# pcb.net
KiCad netlist of a schematic drawn in EAGLE
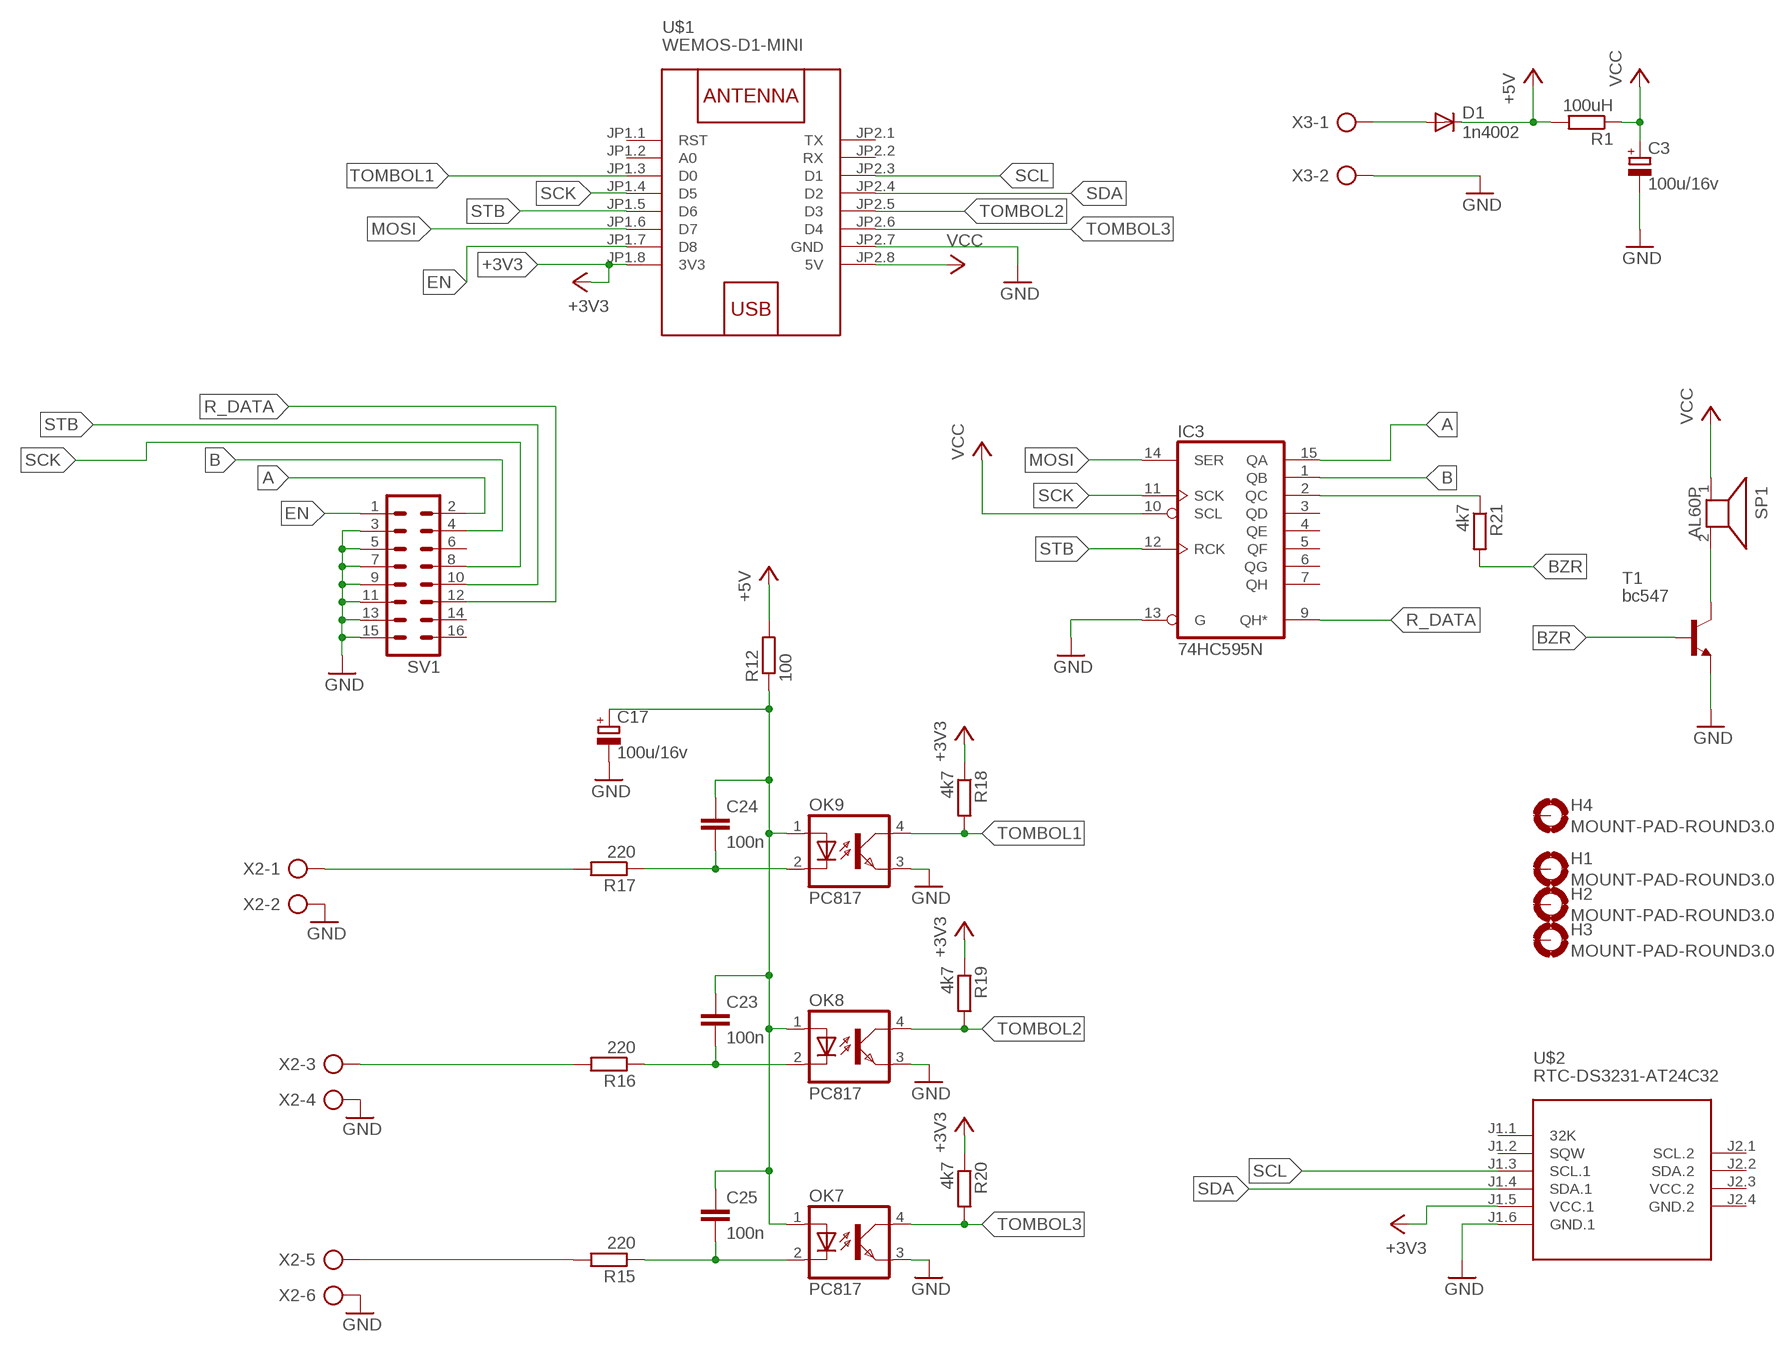
[diagram p0: schematic, sheet 1]

(export (version "E")
  (design (tool "Eeschema 10.0.6"))
  (components
    (comp (ref "C3")
      (value "100u/16v")
      (footprint "eagle-import:E5-4")
      (libsource (lib "eagle-import") (part "CPOL-EUE5-4"))
    )
    (comp (ref "C17")
      (value "100u/16v")
      (footprint "eagle-import:E5-4")
      (libsource (lib "eagle-import") (part "CPOL-EUE5-4"))
    )
    (comp (ref "C23")
      (value "100n")
      (footprint "eagle-import:C050-025X075")
      (libsource (lib "eagle-import") (part "C-EU050-025X075"))
    )
    (comp (ref "C24")
      (value "100n")
      (footprint "eagle-import:C050-025X075")
      (libsource (lib "eagle-import") (part "C-EU050-025X075"))
    )
    (comp (ref "C25")
      (value "100n")
      (footprint "eagle-import:C050-025X075")
      (libsource (lib "eagle-import") (part "C-EU050-025X075"))
    )
    (comp (ref "D1")
      (value "1n4002")
      (footprint "eagle-import:DO35-10")
      (libsource (lib "eagle-import") (part "1N4446"))
    )
    (comp (ref "H1")
      (value "MOUNT-PAD-ROUND3.0")
      (footprint "eagle-import:3,0-PAD")
      (libsource (lib "eagle-import") (part "MOUNT-PAD-ROUND3.0"))
    )
    (comp (ref "H2")
      (value "MOUNT-PAD-ROUND3.0")
      (footprint "eagle-import:3,0-PAD")
      (libsource (lib "eagle-import") (part "MOUNT-PAD-ROUND3.0"))
    )
    (comp (ref "H3")
      (value "MOUNT-PAD-ROUND3.0")
      (footprint "eagle-import:3,0-PAD")
      (libsource (lib "eagle-import") (part "MOUNT-PAD-ROUND3.0"))
    )
    (comp (ref "H4")
      (value "MOUNT-PAD-ROUND3.0")
      (footprint "eagle-import:3,0-PAD")
      (libsource (lib "eagle-import") (part "MOUNT-PAD-ROUND3.0"))
    )
    (comp (ref "IC3")
      (value "74HC595N")
      (footprint "eagle-import:DIL16")
      (libsource (lib "eagle-import") (part "74595NHC"))
    )
    (comp (ref "OK7")
      (value "PC817")
      (footprint "eagle-import:DIL04")
      (fields (field (name "MPN") "PC817X4J000F"))
      (libsource (lib "eagle-import") (part "PC817"))
    )
    (comp (ref "OK8")
      (value "PC817")
      (footprint "eagle-import:DIL04")
      (fields (field (name "MPN") "PC817X4J000F"))
      (libsource (lib "eagle-import") (part "PC817"))
    )
    (comp (ref "OK9")
      (value "PC817")
      (footprint "eagle-import:DIL04")
      (fields (field (name "MPN") "PC817X4J000F"))
      (libsource (lib "eagle-import") (part "PC817"))
    )
    (comp (ref "R1")
      (value "100uH")
      (footprint "eagle-import:0207_10")
      (libsource (lib "eagle-import") (part "R-EU_0207/10"))
    )
    (comp (ref "R12")
      (value "100")
      (footprint "eagle-import:0207_10")
      (libsource (lib "eagle-import") (part "R-EU_0207/10"))
    )
    (comp (ref "R15")
      (value "220")
      (footprint "eagle-import:0207_10")
      (libsource (lib "eagle-import") (part "R-EU_0207/10"))
    )
    (comp (ref "R16")
      (value "220")
      (footprint "eagle-import:0207_10")
      (libsource (lib "eagle-import") (part "R-EU_0207/10"))
    )
    (comp (ref "R17")
      (value "220")
      (footprint "eagle-import:0207_10")
      (libsource (lib "eagle-import") (part "R-EU_0207/10"))
    )
    (comp (ref "R18")
      (value "4k7")
      (footprint "eagle-import:0207_10")
      (libsource (lib "eagle-import") (part "R-EU_0207/10"))
    )
    (comp (ref "R19")
      (value "4k7")
      (footprint "eagle-import:0207_10")
      (libsource (lib "eagle-import") (part "R-EU_0207/10"))
    )
    (comp (ref "R20")
      (value "4k7")
      (footprint "eagle-import:0207_10")
      (libsource (lib "eagle-import") (part "R-EU_0207/10"))
    )
    (comp (ref "R21")
      (value "4k7")
      (footprint "eagle-import:0207_10")
      (libsource (lib "eagle-import") (part "R-EU_0207/10"))
    )
    (comp (ref "SP1")
      (value "AL60P")
      (footprint "eagle-import:AL60P")
      (libsource (lib "eagle-import") (part "AL60P"))
    )
    (comp (ref "SV1")
      (value "ML16")
      (footprint "eagle-import:ML16")
      (libsource (lib "eagle-import") (part "ML16"))
    )
    (comp (ref "T1")
      (value "bc547")
      (footprint "eagle-import:TO92-CBE")
      (libsource (lib "eagle-import") (part "-NPN-TO92-CBEBC547A"))
    )
    (comp (ref "U$1")
      (value "WEMOS-D1-MINI")
      (footprint "eagle-import:WEMOS-D1-MINI")
      (libsource (lib "eagle-import") (part "WEMOS-D1-MINI"))
    )
    (comp (ref "U$2")
      (value "RTC-DS3231-AT24C32")
      (footprint "eagle-import:RTC-DS3231-AT24C32")
      (libsource (lib "eagle-import") (part "RTC-DS3231-AT24C32"))
    )
    (comp (ref "X2")
      (value "AK300/6")
      (footprint "eagle-import:AK300_6")
      (libsource (lib "eagle-import") (part "AK300/6"))
    )
    (comp (ref "X3")
      (value "AK300/2")
      (footprint "eagle-import:AK300_2")
      (libsource (lib "eagle-import") (part "AK300/2"))
    )
  )
  (nets
    (net (code "1") (name "+3V3") (class "Default")
      (node (ref "R18") (pin "1") (pinfunction "1_1") (pintype "passive"))
      (node (ref "R19") (pin "1") (pinfunction "1_1") (pintype "passive"))
      (node (ref "R20") (pin "1") (pinfunction "1_1") (pintype "passive"))
      (node (ref "U$1") (pin "JP1.8") (pinfunction "3V3_JP1.8") (pintype "power_in"))
      (node (ref "U$2") (pin "J1.5") (pinfunction "VCC.1_J1.5") (pintype "power_in"))
    )
    (net (code "2") (name "+5V") (class "Default")
      (node (ref "D1") (pin "C") (pinfunction "C_C") (pintype "passive"))
      (node (ref "R1") (pin "2") (pinfunction "2_2") (pintype "passive"))
      (node (ref "R12") (pin "2") (pinfunction "2_2") (pintype "passive"))
    )
    (net (code "3") (name "/GND.2") (class "Default")
      (node (ref "U$2") (pin "J2.4") (pinfunction "GND.2_J2.4") (pintype "power_in"))
    )
    (net (code "4") (name "/VCC.2") (class "Default")
      (node (ref "U$2") (pin "J2.3") (pinfunction "VCC.2_J2.3") (pintype "power_in"))
    )
    (net (code "5") (name "A") (class "Default")
      (node (ref "IC3") (pin "15") (pinfunction "QA_15") (pintype "tri_state"))
      (node (ref "SV1") (pin "2") (pinfunction "2_2") (pintype "passive"))
    )
    (net (code "6") (name "B") (class "Default")
      (node (ref "IC3") (pin "1") (pinfunction "QB_1") (pintype "tri_state"))
      (node (ref "SV1") (pin "4") (pinfunction "4_4") (pintype "passive"))
    )
    (net (code "7") (name "BZR") (class "Default")
      (node (ref "R21") (pin "2") (pinfunction "2_2") (pintype "passive"))
      (node (ref "T1") (pin "B") (pinfunction "B_B") (pintype "passive"))
    )
    (net (code "8") (name "EN") (class "Default")
      (node (ref "SV1") (pin "1") (pinfunction "1_1") (pintype "passive"))
      (node (ref "U$1") (pin "JP1.7") (pinfunction "D8_JP1.7") (pintype "bidirectional"))
    )
    (net (code "9") (name "GND") (class "Default")
      (node (ref "C17") (pin "-") (pinfunction "-_-") (pintype "passive"))
      (node (ref "C3") (pin "-") (pinfunction "-_-") (pintype "passive"))
      (node (ref "IC3") (pin "13") (pinfunction "G_13") (pintype "input"))
      (node (ref "OK7") (pin "3") (pinfunction "EMIT_3") (pintype "passive"))
      (node (ref "OK8") (pin "3") (pinfunction "EMIT_3") (pintype "passive"))
      (node (ref "OK9") (pin "3") (pinfunction "EMIT_3") (pintype "passive"))
      (node (ref "SV1") (pin "11") (pinfunction "11_11") (pintype "passive"))
      (node (ref "SV1") (pin "13") (pinfunction "13_13") (pintype "passive"))
      (node (ref "SV1") (pin "15") (pinfunction "15_15") (pintype "passive"))
      (node (ref "SV1") (pin "3") (pinfunction "3_3") (pintype "passive"))
      (node (ref "SV1") (pin "5") (pinfunction "5_5") (pintype "passive"))
      (node (ref "SV1") (pin "7") (pinfunction "7_7") (pintype "passive"))
      (node (ref "SV1") (pin "9") (pinfunction "9_9") (pintype "passive"))
      (node (ref "T1") (pin "E") (pinfunction "E_E") (pintype "passive"))
      (node (ref "U$1") (pin "JP2.7") (pinfunction "GND_JP2.7") (pintype "power_in"))
      (node (ref "U$2") (pin "J1.6") (pinfunction "GND.1_J1.6") (pintype "power_in"))
      (node (ref "X2") (pin "2") (pinfunction "KL_2") (pintype "passive"))
      (node (ref "X2") (pin "4") (pinfunction "KL_4") (pintype "passive"))
      (node (ref "X2") (pin "6") (pinfunction "KL_6") (pintype "passive"))
      (node (ref "X3") (pin "2") (pinfunction "KL_2") (pintype "passive"))
    )
    (net (code "10") (name "MOSI") (class "Default")
      (node (ref "IC3") (pin "14") (pinfunction "SER_14") (pintype "input"))
      (node (ref "U$1") (pin "JP1.6") (pinfunction "D7_JP1.6") (pintype "bidirectional"))
    )
    (net (code "11") (name "Net-(IC3A-QC)") (class "Default")
      (node (ref "IC3") (pin "2") (pinfunction "QC_2") (pintype "tri_state"))
      (node (ref "R21") (pin "1") (pinfunction "1_1") (pintype "passive"))
    )
    (net (code "12") (name "Net-(OK7-A)") (class "Default")
      (node (ref "C17") (pin "+") (pinfunction "+_+") (pintype "passive"))
      (node (ref "C23") (pin "1") (pinfunction "1_1") (pintype "passive"))
      (node (ref "C24") (pin "1") (pinfunction "1_1") (pintype "passive"))
      (node (ref "C25") (pin "1") (pinfunction "1_1") (pintype "passive"))
      (node (ref "OK7") (pin "1") (pinfunction "A_1") (pintype "passive"))
      (node (ref "OK8") (pin "1") (pinfunction "A_1") (pintype "passive"))
      (node (ref "OK9") (pin "1") (pinfunction "A_1") (pintype "passive"))
      (node (ref "R12") (pin "1") (pinfunction "1_1") (pintype "passive"))
    )
    (net (code "13") (name "Net-(OK7-C)") (class "Default")
      (node (ref "C25") (pin "2") (pinfunction "2_2") (pintype "passive"))
      (node (ref "OK7") (pin "2") (pinfunction "C_2") (pintype "passive"))
      (node (ref "R15") (pin "1") (pinfunction "1_1") (pintype "passive"))
    )
    (net (code "14") (name "Net-(OK8-C)") (class "Default")
      (node (ref "C23") (pin "2") (pinfunction "2_2") (pintype "passive"))
      (node (ref "OK8") (pin "2") (pinfunction "C_2") (pintype "passive"))
      (node (ref "R16") (pin "1") (pinfunction "1_1") (pintype "passive"))
    )
    (net (code "15") (name "Net-(OK9-C)") (class "Default")
      (node (ref "C24") (pin "2") (pinfunction "2_2") (pintype "passive"))
      (node (ref "OK9") (pin "2") (pinfunction "C_2") (pintype "passive"))
      (node (ref "R17") (pin "1") (pinfunction "1_1") (pintype "passive"))
    )
    (net (code "16") (name "Net-(SP1-Pad2)") (class "Default")
      (node (ref "SP1") (pin "2") (pinfunction "2_2") (pintype "passive"))
      (node (ref "T1") (pin "C") (pinfunction "C_C") (pintype "passive"))
    )
    (net (code "17") (name "Net-(X2A-KL)") (class "Default")
      (node (ref "R17") (pin "2") (pinfunction "2_2") (pintype "passive"))
      (node (ref "X2") (pin "1") (pinfunction "KL_1") (pintype "passive"))
    )
    (net (code "18") (name "Net-(X2C-KL)") (class "Default")
      (node (ref "R16") (pin "2") (pinfunction "2_2") (pintype "passive"))
      (node (ref "X2") (pin "3") (pinfunction "KL_3") (pintype "passive"))
    )
    (net (code "19") (name "Net-(X2E-KL)") (class "Default")
      (node (ref "R15") (pin "2") (pinfunction "2_2") (pintype "passive"))
      (node (ref "X2") (pin "5") (pinfunction "KL_5") (pintype "passive"))
    )
    (net (code "20") (name "Net-(X3A-KL)") (class "Default")
      (node (ref "D1") (pin "A") (pinfunction "A_A") (pintype "passive"))
      (node (ref "X3") (pin "1") (pinfunction "KL_1") (pintype "passive"))
    )
    (net (code "21") (name "R_DATA") (class "Default")
      (node (ref "IC3") (pin "9") (pinfunction "QH*_9") (pintype "tri_state"))
      (node (ref "SV1") (pin "12") (pinfunction "12_12") (pintype "passive"))
    )
    (net (code "22") (name "SCK") (class "Default")
      (node (ref "IC3") (pin "11") (pinfunction "SCK_11") (pintype "input"))
      (node (ref "SV1") (pin "8") (pinfunction "8_8") (pintype "passive"))
      (node (ref "U$1") (pin "JP1.4") (pinfunction "D5_JP1.4") (pintype "bidirectional"))
    )
    (net (code "23") (name "SCL") (class "Default")
      (node (ref "U$1") (pin "JP2.3") (pinfunction "D1_JP2.3") (pintype "bidirectional"))
      (node (ref "U$2") (pin "J1.3") (pinfunction "SCL.1_J1.3") (pintype "bidirectional"))
    )
    (net (code "24") (name "SDA") (class "Default")
      (node (ref "U$1") (pin "JP2.4") (pinfunction "D2_JP2.4") (pintype "bidirectional"))
      (node (ref "U$2") (pin "J1.4") (pinfunction "SDA.1_J1.4") (pintype "bidirectional"))
    )
    (net (code "25") (name "STB") (class "Default")
      (node (ref "IC3") (pin "12") (pinfunction "RCK_12") (pintype "input"))
      (node (ref "SV1") (pin "10") (pinfunction "10_10") (pintype "passive"))
      (node (ref "U$1") (pin "JP1.5") (pinfunction "D6_JP1.5") (pintype "bidirectional"))
    )
    (net (code "26") (name "TOMBOL1") (class "Default")
      (node (ref "OK9") (pin "4") (pinfunction "COL_4") (pintype "passive"))
      (node (ref "R18") (pin "2") (pinfunction "2_2") (pintype "passive"))
      (node (ref "U$1") (pin "JP1.3") (pinfunction "D0_JP1.3") (pintype "bidirectional"))
    )
    (net (code "27") (name "TOMBOL2") (class "Default")
      (node (ref "OK8") (pin "4") (pinfunction "COL_4") (pintype "passive"))
      (node (ref "R19") (pin "2") (pinfunction "2_2") (pintype "passive"))
      (node (ref "U$1") (pin "JP2.5") (pinfunction "D3_JP2.5") (pintype "bidirectional"))
    )
    (net (code "28") (name "TOMBOL3") (class "Default")
      (node (ref "OK7") (pin "4") (pinfunction "COL_4") (pintype "passive"))
      (node (ref "R20") (pin "2") (pinfunction "2_2") (pintype "passive"))
      (node (ref "U$1") (pin "JP2.6") (pinfunction "D4_JP2.6") (pintype "bidirectional"))
    )
    (net (code "29") (name "VCC") (class "Default")
      (node (ref "C3") (pin "+") (pinfunction "+_+") (pintype "passive"))
      (node (ref "IC3") (pin "10") (pinfunction "SCL_10") (pintype "input"))
      (node (ref "R1") (pin "1") (pinfunction "1_1") (pintype "passive"))
      (node (ref "SP1") (pin "1") (pinfunction "1_1") (pintype "passive"))
      (node (ref "U$1") (pin "JP2.8") (pinfunction "5V_JP2.8") (pintype "power_in"))
    )
    (net (code "30") (name "unconnected-(H1-MOUNT-PadB3,0)") (class "Default")
      (node (ref "H1") (pin "B3,0") (pinfunction "MOUNT_B3,0") (pintype "passive"))
    )
    (net (code "31") (name "unconnected-(H2-MOUNT-PadB3,0)") (class "Default")
      (node (ref "H2") (pin "B3,0") (pinfunction "MOUNT_B3,0") (pintype "passive"))
    )
    (net (code "32") (name "unconnected-(H3-MOUNT-PadB3,0)") (class "Default")
      (node (ref "H3") (pin "B3,0") (pinfunction "MOUNT_B3,0") (pintype "passive"))
    )
    (net (code "33") (name "unconnected-(H4-MOUNT-PadB3,0)") (class "Default")
      (node (ref "H4") (pin "B3,0") (pinfunction "MOUNT_B3,0") (pintype "passive"))
    )
    (net (code "34") (name "unconnected-(IC3A-QD-Pad3)") (class "Default")
      (node (ref "IC3") (pin "3") (pinfunction "QD_3") (pintype "tri_state"))
    )
    (net (code "35") (name "unconnected-(IC3A-QE-Pad4)") (class "Default")
      (node (ref "IC3") (pin "4") (pinfunction "QE_4") (pintype "tri_state"))
    )
    (net (code "36") (name "unconnected-(IC3A-QF-Pad5)") (class "Default")
      (node (ref "IC3") (pin "5") (pinfunction "QF_5") (pintype "tri_state"))
    )
    (net (code "37") (name "unconnected-(IC3A-QG-Pad6)") (class "Default")
      (node (ref "IC3") (pin "6") (pinfunction "QG_6") (pintype "tri_state"))
    )
    (net (code "38") (name "unconnected-(IC3A-QH-Pad7)") (class "Default")
      (node (ref "IC3") (pin "7") (pinfunction "QH_7") (pintype "tri_state"))
    )
    (net (code "39") (name "unconnected-(SV1-Pad6)") (class "Default")
      (node (ref "SV1") (pin "6") (pinfunction "6_6") (pintype "passive"))
    )
    (net (code "40") (name "unconnected-(SV1-Pad14)") (class "Default")
      (node (ref "SV1") (pin "14") (pinfunction "14_14") (pintype "passive"))
    )
    (net (code "41") (name "unconnected-(SV1-Pad16)") (class "Default")
      (node (ref "SV1") (pin "16") (pinfunction "16_16") (pintype "passive"))
    )
    (net (code "42") (name "unconnected-(U$1-A0-PadJP1.2)") (class "Default")
      (node (ref "U$1") (pin "JP1.2") (pinfunction "A0_JP1.2") (pintype "bidirectional"))
    )
    (net (code "43") (name "unconnected-(U$1-RST-PadJP1.1)") (class "Default")
      (node (ref "U$1") (pin "JP1.1") (pinfunction "RST_JP1.1") (pintype "bidirectional"))
    )
    (net (code "44") (name "unconnected-(U$1-RX-PadJP2.2)") (class "Default")
      (node (ref "U$1") (pin "JP2.2") (pinfunction "RX_JP2.2") (pintype "bidirectional"))
    )
    (net (code "45") (name "unconnected-(U$1-TX-PadJP2.1)") (class "Default")
      (node (ref "U$1") (pin "JP2.1") (pinfunction "TX_JP2.1") (pintype "bidirectional"))
    )
    (net (code "46") (name "unconnected-(U$2-32K-PadJ1.1)") (class "Default")
      (node (ref "U$2") (pin "J1.1") (pinfunction "32K_J1.1") (pintype "bidirectional"))
    )
    (net (code "47") (name "unconnected-(U$2-SCL.2-PadJ2.1)") (class "Default")
      (node (ref "U$2") (pin "J2.1") (pinfunction "SCL.2_J2.1") (pintype "bidirectional"))
    )
    (net (code "48") (name "unconnected-(U$2-SDA.2-PadJ2.2)") (class "Default")
      (node (ref "U$2") (pin "J2.2") (pinfunction "SDA.2_J2.2") (pintype "bidirectional"))
    )
    (net (code "49") (name "unconnected-(U$2-SQW-PadJ1.2)") (class "Default")
      (node (ref "U$2") (pin "J1.2") (pinfunction "SQW_J1.2") (pintype "bidirectional"))
    )
  )
)
